# Cyclone_Keychain_SSOP28.net
KiCad netlist of a schematic drawn in EAGLE
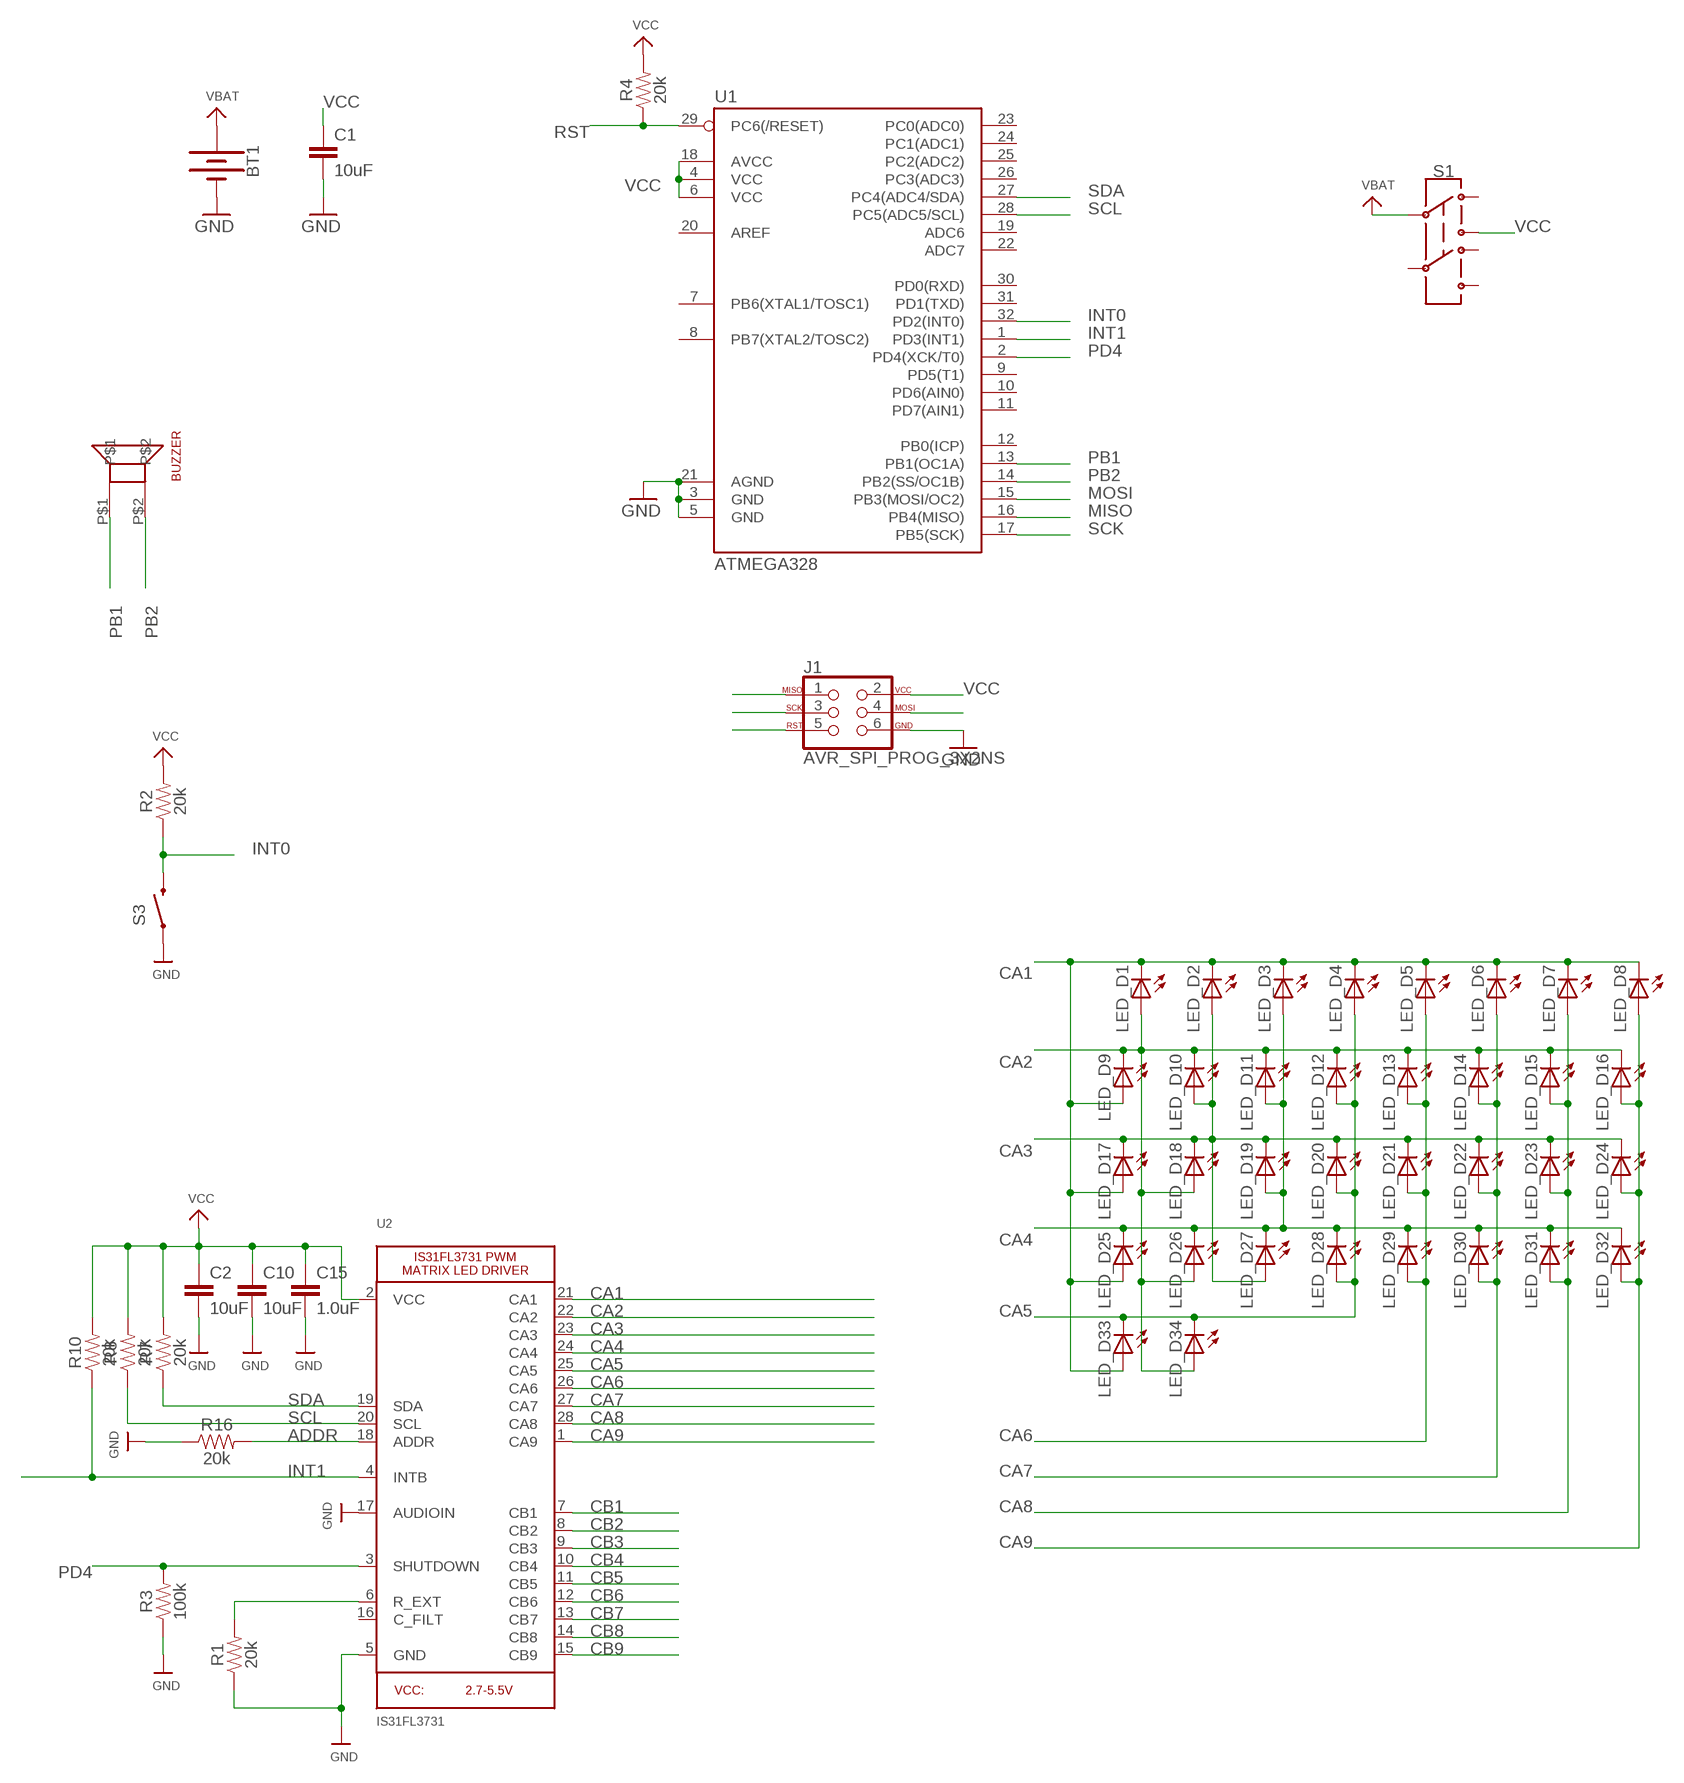
[diagram p0: schematic, sheet 1]

(export (version "E")
  (design (tool "Eeschema 10.0.6"))
  (components
    (comp (ref "BT1")
      (value "BATTERY-20MM_PTH_WIDEPOS")
      (footprint "eagle-import:BATTCOM_20MM_PTH_WIDEPOS")
      (libsource (lib "eagle-import") (part "BATTERY-20MM_PTH_WIDEPOS"))
    )
    (comp (ref "C1")
      (value "10uF")
      (footprint "eagle-import:0805")
      (libsource (lib "eagle-import") (part "10UF-0805-10V-10%"))
    )
    (comp (ref "C2")
      (value "10uF")
      (footprint "eagle-import:0805")
      (libsource (lib "eagle-import") (part "10UF-0805-10V-10%"))
    )
    (comp (ref "C10")
      (value "10uF")
      (footprint "eagle-import:0805")
      (libsource (lib "eagle-import") (part "10UF-0805-10V-10%"))
    )
    (comp (ref "C15")
      (value "1.0uF")
      (footprint "eagle-import:0805")
      (libsource (lib "eagle-import") (part "1.0UF-0805-25V-10%"))
    )
    (comp (ref "J1")
      (value "AVR_SPI_PROG_3X2NS")
      (footprint "eagle-import:2X3-NS")
      (libsource (lib "eagle-import") (part "AVR_SPI_PROG_3X2NS"))
    )
    (comp (ref "LED_D1")
      (value "LEDCHIP-LED0805")
      (footprint "eagle-import:CHIP-LED0805")
      (libsource (lib "eagle-import") (part "LEDCHIP-LED0805"))
    )
    (comp (ref "LED_D2")
      (value "LEDCHIP-LED0805")
      (footprint "eagle-import:CHIP-LED0805")
      (libsource (lib "eagle-import") (part "LEDCHIP-LED0805"))
    )
    (comp (ref "LED_D3")
      (value "LEDCHIP-LED0805")
      (footprint "eagle-import:CHIP-LED0805")
      (libsource (lib "eagle-import") (part "LEDCHIP-LED0805"))
    )
    (comp (ref "LED_D4")
      (value "LEDCHIP-LED0805")
      (footprint "eagle-import:CHIP-LED0805")
      (libsource (lib "eagle-import") (part "LEDCHIP-LED0805"))
    )
    (comp (ref "LED_D5")
      (value "LEDCHIP-LED0805")
      (footprint "eagle-import:CHIP-LED0805")
      (libsource (lib "eagle-import") (part "LEDCHIP-LED0805"))
    )
    (comp (ref "LED_D6")
      (value "LEDCHIP-LED0805")
      (footprint "eagle-import:CHIP-LED0805")
      (libsource (lib "eagle-import") (part "LEDCHIP-LED0805"))
    )
    (comp (ref "LED_D7")
      (value "LEDCHIP-LED0805")
      (footprint "eagle-import:CHIP-LED0805")
      (libsource (lib "eagle-import") (part "LEDCHIP-LED0805"))
    )
    (comp (ref "LED_D8")
      (value "LEDCHIP-LED0805")
      (footprint "eagle-import:CHIP-LED0805")
      (libsource (lib "eagle-import") (part "LEDCHIP-LED0805"))
    )
    (comp (ref "LED_D9")
      (value "LEDCHIP-LED0805")
      (footprint "eagle-import:CHIP-LED0805")
      (libsource (lib "eagle-import") (part "LEDCHIP-LED0805"))
    )
    (comp (ref "LED_D10")
      (value "LEDCHIP-LED0805")
      (footprint "eagle-import:CHIP-LED0805")
      (libsource (lib "eagle-import") (part "LEDCHIP-LED0805"))
    )
    (comp (ref "LED_D11")
      (value "LEDCHIP-LED0805")
      (footprint "eagle-import:CHIP-LED0805")
      (libsource (lib "eagle-import") (part "LEDCHIP-LED0805"))
    )
    (comp (ref "LED_D12")
      (value "LEDCHIP-LED0805")
      (footprint "eagle-import:CHIP-LED0805")
      (libsource (lib "eagle-import") (part "LEDCHIP-LED0805"))
    )
    (comp (ref "LED_D13")
      (value "LEDCHIP-LED0805")
      (footprint "eagle-import:CHIP-LED0805")
      (libsource (lib "eagle-import") (part "LEDCHIP-LED0805"))
    )
    (comp (ref "LED_D14")
      (value "LEDCHIP-LED0805")
      (footprint "eagle-import:CHIP-LED0805")
      (libsource (lib "eagle-import") (part "LEDCHIP-LED0805"))
    )
    (comp (ref "LED_D15")
      (value "LEDCHIP-LED0805")
      (footprint "eagle-import:CHIP-LED0805")
      (libsource (lib "eagle-import") (part "LEDCHIP-LED0805"))
    )
    (comp (ref "LED_D16")
      (value "LEDCHIP-LED0805")
      (footprint "eagle-import:CHIP-LED0805")
      (libsource (lib "eagle-import") (part "LEDCHIP-LED0805"))
    )
    (comp (ref "LED_D17")
      (value "LEDCHIP-LED0805")
      (footprint "eagle-import:CHIP-LED0805")
      (libsource (lib "eagle-import") (part "LEDCHIP-LED0805"))
    )
    (comp (ref "LED_D18")
      (value "LEDCHIP-LED0805")
      (footprint "eagle-import:CHIP-LED0805")
      (libsource (lib "eagle-import") (part "LEDCHIP-LED0805"))
    )
    (comp (ref "LED_D19")
      (value "LEDCHIP-LED0805")
      (footprint "eagle-import:CHIP-LED0805")
      (libsource (lib "eagle-import") (part "LEDCHIP-LED0805"))
    )
    (comp (ref "LED_D20")
      (value "LEDCHIP-LED0805")
      (footprint "eagle-import:CHIP-LED0805")
      (libsource (lib "eagle-import") (part "LEDCHIP-LED0805"))
    )
    (comp (ref "LED_D21")
      (value "LEDCHIP-LED0805")
      (footprint "eagle-import:CHIP-LED0805")
      (libsource (lib "eagle-import") (part "LEDCHIP-LED0805"))
    )
    (comp (ref "LED_D22")
      (value "LEDCHIP-LED0805")
      (footprint "eagle-import:CHIP-LED0805")
      (libsource (lib "eagle-import") (part "LEDCHIP-LED0805"))
    )
    (comp (ref "LED_D23")
      (value "LEDCHIP-LED0805")
      (footprint "eagle-import:CHIP-LED0805")
      (libsource (lib "eagle-import") (part "LEDCHIP-LED0805"))
    )
    (comp (ref "LED_D24")
      (value "LEDCHIP-LED0805")
      (footprint "eagle-import:CHIP-LED0805")
      (libsource (lib "eagle-import") (part "LEDCHIP-LED0805"))
    )
    (comp (ref "LED_D25")
      (value "LEDCHIP-LED0805")
      (footprint "eagle-import:CHIP-LED0805")
      (libsource (lib "eagle-import") (part "LEDCHIP-LED0805"))
    )
    (comp (ref "LED_D26")
      (value "LEDCHIP-LED0805")
      (footprint "eagle-import:CHIP-LED0805")
      (libsource (lib "eagle-import") (part "LEDCHIP-LED0805"))
    )
    (comp (ref "LED_D27")
      (value "LEDCHIP-LED0805")
      (footprint "eagle-import:CHIP-LED0805")
      (libsource (lib "eagle-import") (part "LEDCHIP-LED0805"))
    )
    (comp (ref "LED_D28")
      (value "LEDCHIP-LED0805")
      (footprint "eagle-import:CHIP-LED0805")
      (libsource (lib "eagle-import") (part "LEDCHIP-LED0805"))
    )
    (comp (ref "LED_D29")
      (value "LEDCHIP-LED0805")
      (footprint "eagle-import:CHIP-LED0805")
      (libsource (lib "eagle-import") (part "LEDCHIP-LED0805"))
    )
    (comp (ref "LED_D30")
      (value "LEDCHIP-LED0805")
      (footprint "eagle-import:CHIP-LED0805")
      (libsource (lib "eagle-import") (part "LEDCHIP-LED0805"))
    )
    (comp (ref "LED_D31")
      (value "LEDCHIP-LED0805")
      (footprint "eagle-import:CHIP-LED0805")
      (libsource (lib "eagle-import") (part "LEDCHIP-LED0805"))
    )
    (comp (ref "LED_D32")
      (value "LEDCHIP-LED0805")
      (footprint "eagle-import:CHIP-LED0805")
      (libsource (lib "eagle-import") (part "LEDCHIP-LED0805"))
    )
    (comp (ref "LED_D33")
      (value "LEDCHIP-LED0805")
      (footprint "eagle-import:CHIP-LED0805")
      (libsource (lib "eagle-import") (part "LEDCHIP-LED0805"))
    )
    (comp (ref "LED_D34")
      (value "LEDCHIP-LED0805")
      (footprint "eagle-import:CHIP-LED0805")
      (libsource (lib "eagle-import") (part "LEDCHIP-LED0805"))
    )
    (comp (ref "R1")
      (value "20k")
      (footprint "eagle-import:0805")
      (libsource (lib "eagle-import") (part "20KOHM-0805-1/8W-5%"))
    )
    (comp (ref "R2")
      (value "20k")
      (footprint "eagle-import:0805")
      (libsource (lib "eagle-import") (part "20KOHM-0805-1/8W-5%"))
    )
    (comp (ref "R3")
      (value "100k")
      (footprint "eagle-import:0805")
      (libsource (lib "eagle-import") (part "20KOHM-0805-1/8W-5%"))
    )
    (comp (ref "R4")
      (value "20k")
      (footprint "eagle-import:0805")
      (libsource (lib "eagle-import") (part "20KOHM-0805-1/8W-5%"))
    )
    (comp (ref "R7")
      (value "20k")
      (footprint "eagle-import:0805")
      (libsource (lib "eagle-import") (part "20KOHM-0805-1/8W-5%"))
    )
    (comp (ref "R8")
      (value "20k")
      (footprint "eagle-import:0805")
      (libsource (lib "eagle-import") (part "20KOHM-0805-1/8W-5%"))
    )
    (comp (ref "R10")
      (value "20k")
      (footprint "eagle-import:0805")
      (libsource (lib "eagle-import") (part "20KOHM-0805-1/8W-5%"))
    )
    (comp (ref "R16")
      (value "20k")
      (footprint "eagle-import:0805")
      (libsource (lib "eagle-import") (part "20KOHM-0805-1/8W-5%"))
    )
    (comp (ref "S1")
      (value "SWITCH-DPDT-SMD-AYZ0202")
      (footprint "eagle-import:SWITCH_DPDT_SMD_AYZ0202")
      (libsource (lib "eagle-import") (part "SWITCH-DPDT-SMD-AYZ0202"))
    )
    (comp (ref "S3")
      (value "SWITCH-MOMENTARY-2SMD")
      (footprint "eagle-import:TACTILE_SWITCH_SMD")
      (libsource (lib "eagle-import") (part "SWITCH-MOMENTARY-2SMD"))
    )
    (comp (ref "U$11")
      (value "PIEZO_BUZZER_SMT")
      (footprint "eagle-import:PIEZO_BUZZER_SMT")
      (libsource (lib "eagle-import") (part "PIEZO_BUZZER_SMT"))
    )
    (comp (ref "U1")
      (value "ATMEGA328")
      (footprint "eagle-import:TQFP32-08")
      (libsource (lib "eagle-import") (part "ATMEGA328P_TQFP"))
    )
    (comp (ref "U2")
      (value "IS31FL3731")
      (footprint "eagle-import:SSOP28DB")
      (libsource (lib "eagle-import") (part "IS31FL3731SSOP"))
    )
  )
  (nets
    (net (code "1") (name "/ADDR") (class "Default")
      (node (ref "R16") (pin "2") (pinfunction "2_2") (pintype "passive"))
      (node (ref "U2") (pin "18") (pinfunction "ADDR_18") (pintype "bidirectional"))
    )
    (net (code "2") (name "/CA1") (class "Default")
      (node (ref "LED_D1") (pin "C") (pinfunction "C_C") (pintype "passive"))
      (node (ref "LED_D17") (pin "A") (pinfunction "A_A") (pintype "passive"))
      (node (ref "LED_D2") (pin "C") (pinfunction "C_C") (pintype "passive"))
      (node (ref "LED_D25") (pin "A") (pinfunction "A_A") (pintype "passive"))
      (node (ref "LED_D3") (pin "C") (pinfunction "C_C") (pintype "passive"))
      (node (ref "LED_D33") (pin "A") (pinfunction "A_A") (pintype "passive"))
      (node (ref "LED_D4") (pin "C") (pinfunction "C_C") (pintype "passive"))
      (node (ref "LED_D5") (pin "C") (pinfunction "C_C") (pintype "passive"))
      (node (ref "LED_D6") (pin "C") (pinfunction "C_C") (pintype "passive"))
      (node (ref "LED_D7") (pin "C") (pinfunction "C_C") (pintype "passive"))
      (node (ref "LED_D8") (pin "C") (pinfunction "C_C") (pintype "passive"))
      (node (ref "LED_D9") (pin "A") (pinfunction "A_A") (pintype "passive"))
      (node (ref "U2") (pin "21") (pinfunction "CA1_21") (pintype "bidirectional"))
    )
    (net (code "3") (name "/CA2") (class "Default")
      (node (ref "LED_D1") (pin "A") (pinfunction "A_A") (pintype "passive"))
      (node (ref "LED_D10") (pin "C") (pinfunction "C_C") (pintype "passive"))
      (node (ref "LED_D11") (pin "C") (pinfunction "C_C") (pintype "passive"))
      (node (ref "LED_D12") (pin "C") (pinfunction "C_C") (pintype "passive"))
      (node (ref "LED_D13") (pin "C") (pinfunction "C_C") (pintype "passive"))
      (node (ref "LED_D14") (pin "C") (pinfunction "C_C") (pintype "passive"))
      (node (ref "LED_D15") (pin "C") (pinfunction "C_C") (pintype "passive"))
      (node (ref "LED_D16") (pin "C") (pinfunction "C_C") (pintype "passive"))
      (node (ref "LED_D18") (pin "A") (pinfunction "A_A") (pintype "passive"))
      (node (ref "LED_D26") (pin "A") (pinfunction "A_A") (pintype "passive"))
      (node (ref "LED_D34") (pin "A") (pinfunction "A_A") (pintype "passive"))
      (node (ref "LED_D9") (pin "C") (pinfunction "C_C") (pintype "passive"))
      (node (ref "U2") (pin "22") (pinfunction "CA2_22") (pintype "bidirectional"))
    )
    (net (code "4") (name "/CA3") (class "Default")
      (node (ref "LED_D10") (pin "A") (pinfunction "A_A") (pintype "passive"))
      (node (ref "LED_D17") (pin "C") (pinfunction "C_C") (pintype "passive"))
      (node (ref "LED_D18") (pin "C") (pinfunction "C_C") (pintype "passive"))
      (node (ref "LED_D19") (pin "C") (pinfunction "C_C") (pintype "passive"))
      (node (ref "LED_D2") (pin "A") (pinfunction "A_A") (pintype "passive"))
      (node (ref "LED_D20") (pin "C") (pinfunction "C_C") (pintype "passive"))
      (node (ref "LED_D21") (pin "C") (pinfunction "C_C") (pintype "passive"))
      (node (ref "LED_D22") (pin "C") (pinfunction "C_C") (pintype "passive"))
      (node (ref "LED_D23") (pin "C") (pinfunction "C_C") (pintype "passive"))
      (node (ref "LED_D24") (pin "C") (pinfunction "C_C") (pintype "passive"))
      (node (ref "LED_D27") (pin "A") (pinfunction "A_A") (pintype "passive"))
      (node (ref "U2") (pin "23") (pinfunction "CA3_23") (pintype "bidirectional"))
    )
    (net (code "5") (name "/CA4") (class "Default")
      (node (ref "LED_D11") (pin "A") (pinfunction "A_A") (pintype "passive"))
      (node (ref "LED_D19") (pin "A") (pinfunction "A_A") (pintype "passive"))
      (node (ref "LED_D25") (pin "C") (pinfunction "C_C") (pintype "passive"))
      (node (ref "LED_D26") (pin "C") (pinfunction "C_C") (pintype "passive"))
      (node (ref "LED_D27") (pin "C") (pinfunction "C_C") (pintype "passive"))
      (node (ref "LED_D28") (pin "C") (pinfunction "C_C") (pintype "passive"))
      (node (ref "LED_D29") (pin "C") (pinfunction "C_C") (pintype "passive"))
      (node (ref "LED_D3") (pin "A") (pinfunction "A_A") (pintype "passive"))
      (node (ref "LED_D30") (pin "C") (pinfunction "C_C") (pintype "passive"))
      (node (ref "LED_D31") (pin "C") (pinfunction "C_C") (pintype "passive"))
      (node (ref "LED_D32") (pin "C") (pinfunction "C_C") (pintype "passive"))
      (node (ref "U2") (pin "24") (pinfunction "CA4_24") (pintype "bidirectional"))
    )
    (net (code "6") (name "/CA5") (class "Default")
      (node (ref "LED_D12") (pin "A") (pinfunction "A_A") (pintype "passive"))
      (node (ref "LED_D20") (pin "A") (pinfunction "A_A") (pintype "passive"))
      (node (ref "LED_D28") (pin "A") (pinfunction "A_A") (pintype "passive"))
      (node (ref "LED_D33") (pin "C") (pinfunction "C_C") (pintype "passive"))
      (node (ref "LED_D34") (pin "C") (pinfunction "C_C") (pintype "passive"))
      (node (ref "LED_D4") (pin "A") (pinfunction "A_A") (pintype "passive"))
      (node (ref "U2") (pin "25") (pinfunction "CA5_25") (pintype "bidirectional"))
    )
    (net (code "7") (name "/CA6") (class "Default")
      (node (ref "LED_D13") (pin "A") (pinfunction "A_A") (pintype "passive"))
      (node (ref "LED_D21") (pin "A") (pinfunction "A_A") (pintype "passive"))
      (node (ref "LED_D29") (pin "A") (pinfunction "A_A") (pintype "passive"))
      (node (ref "LED_D5") (pin "A") (pinfunction "A_A") (pintype "passive"))
      (node (ref "U2") (pin "26") (pinfunction "CA6_26") (pintype "bidirectional"))
    )
    (net (code "8") (name "/CA7") (class "Default")
      (node (ref "LED_D14") (pin "A") (pinfunction "A_A") (pintype "passive"))
      (node (ref "LED_D22") (pin "A") (pinfunction "A_A") (pintype "passive"))
      (node (ref "LED_D30") (pin "A") (pinfunction "A_A") (pintype "passive"))
      (node (ref "LED_D6") (pin "A") (pinfunction "A_A") (pintype "passive"))
      (node (ref "U2") (pin "27") (pinfunction "CA7_27") (pintype "bidirectional"))
    )
    (net (code "9") (name "/CA8") (class "Default")
      (node (ref "LED_D15") (pin "A") (pinfunction "A_A") (pintype "passive"))
      (node (ref "LED_D23") (pin "A") (pinfunction "A_A") (pintype "passive"))
      (node (ref "LED_D31") (pin "A") (pinfunction "A_A") (pintype "passive"))
      (node (ref "LED_D7") (pin "A") (pinfunction "A_A") (pintype "passive"))
      (node (ref "U2") (pin "28") (pinfunction "CA8_28") (pintype "bidirectional"))
    )
    (net (code "10") (name "/CA9") (class "Default")
      (node (ref "LED_D16") (pin "A") (pinfunction "A_A") (pintype "passive"))
      (node (ref "LED_D24") (pin "A") (pinfunction "A_A") (pintype "passive"))
      (node (ref "LED_D32") (pin "A") (pinfunction "A_A") (pintype "passive"))
      (node (ref "LED_D8") (pin "A") (pinfunction "A_A") (pintype "passive"))
      (node (ref "U2") (pin "1") (pinfunction "CA9_1") (pintype "bidirectional"))
    )
    (net (code "11") (name "/CB1") (class "Default")
      (node (ref "U2") (pin "7") (pinfunction "CB1_7") (pintype "bidirectional"))
    )
    (net (code "12") (name "/CB2") (class "Default")
      (node (ref "U2") (pin "8") (pinfunction "CB2_8") (pintype "bidirectional"))
    )
    (net (code "13") (name "/CB3") (class "Default")
      (node (ref "U2") (pin "9") (pinfunction "CB3_9") (pintype "bidirectional"))
    )
    (net (code "14") (name "/CB4") (class "Default")
      (node (ref "U2") (pin "10") (pinfunction "CB4_10") (pintype "bidirectional"))
    )
    (net (code "15") (name "/CB5") (class "Default")
      (node (ref "U2") (pin "11") (pinfunction "CB5_11") (pintype "bidirectional"))
    )
    (net (code "16") (name "/CB6") (class "Default")
      (node (ref "U2") (pin "12") (pinfunction "CB6_12") (pintype "bidirectional"))
    )
    (net (code "17") (name "/CB7") (class "Default")
      (node (ref "U2") (pin "13") (pinfunction "CB7_13") (pintype "bidirectional"))
    )
    (net (code "18") (name "/CB8") (class "Default")
      (node (ref "U2") (pin "14") (pinfunction "CB8_14") (pintype "bidirectional"))
    )
    (net (code "19") (name "/CB9") (class "Default")
      (node (ref "U2") (pin "15") (pinfunction "CB9_15") (pintype "bidirectional"))
    )
    (net (code "20") (name "/INT0") (class "Default")
      (node (ref "R2") (pin "1") (pinfunction "1_1") (pintype "passive"))
      (node (ref "S3") (pin "3") (pinfunction "2_3") (pintype "passive"))
      (node (ref "U1") (pin "32") (pinfunction "PD2(INT0)_32") (pintype "bidirectional"))
    )
    (net (code "21") (name "/INT1") (class "Default")
      (node (ref "R10") (pin "1") (pinfunction "1_1") (pintype "passive"))
      (node (ref "U1") (pin "1") (pinfunction "PD3(INT1)_1") (pintype "bidirectional"))
      (node (ref "U2") (pin "4") (pinfunction "INTB_4") (pintype "output"))
    )
    (net (code "22") (name "/MISO") (class "Default")
      (node (ref "J1") (pin "1") (pinfunction "1_1") (pintype "passive"))
      (node (ref "U1") (pin "16") (pinfunction "PB4(MISO)_16") (pintype "bidirectional"))
    )
    (net (code "23") (name "/MOSI") (class "Default")
      (node (ref "J1") (pin "4") (pinfunction "4_4") (pintype "passive"))
      (node (ref "U1") (pin "15") (pinfunction "PB3(MOSI/OC2)_15") (pintype "bidirectional"))
    )
    (net (code "24") (name "/PB1") (class "Default")
      (node (ref "U$11") (pin "P$1") (pinfunction "P$1_P$1") (pintype "bidirectional"))
      (node (ref "U1") (pin "13") (pinfunction "PB1(OC1A)_13") (pintype "bidirectional"))
    )
    (net (code "25") (name "/PB2") (class "Default")
      (node (ref "U$11") (pin "P$2") (pinfunction "P$2_P$2") (pintype "bidirectional"))
      (node (ref "U1") (pin "14") (pinfunction "PB2(SS/OC1B)_14") (pintype "bidirectional"))
    )
    (net (code "26") (name "/PD4") (class "Default")
      (node (ref "R3") (pin "2") (pinfunction "2_2") (pintype "passive"))
      (node (ref "U1") (pin "2") (pinfunction "PD4(XCK/T0)_2") (pintype "bidirectional"))
      (node (ref "U2") (pin "3") (pinfunction "SHUTDOWN_3") (pintype "input"))
    )
    (net (code "27") (name "/RST") (class "Default")
      (node (ref "J1") (pin "5") (pinfunction "5_5") (pintype "passive"))
      (node (ref "R4") (pin "1") (pinfunction "1_1") (pintype "passive"))
      (node (ref "U1") (pin "29") (pinfunction "PC6(/RESET)_29") (pintype "bidirectional"))
    )
    (net (code "28") (name "/SCK") (class "Default")
      (node (ref "J1") (pin "3") (pinfunction "3_3") (pintype "passive"))
      (node (ref "U1") (pin "17") (pinfunction "PB5(SCK)_17") (pintype "bidirectional"))
    )
    (net (code "29") (name "/SCL") (class "Default")
      (node (ref "R8") (pin "1") (pinfunction "1_1") (pintype "passive"))
      (node (ref "U1") (pin "28") (pinfunction "PC5(ADC5/SCL)_28") (pintype "bidirectional"))
      (node (ref "U2") (pin "20") (pinfunction "SCL_20") (pintype "bidirectional"))
    )
    (net (code "30") (name "/SDA") (class "Default")
      (node (ref "R7") (pin "1") (pinfunction "1_1") (pintype "passive"))
      (node (ref "U1") (pin "27") (pinfunction "PC4(ADC4/SDA)_27") (pintype "bidirectional"))
      (node (ref "U2") (pin "19") (pinfunction "SDA_19") (pintype "bidirectional"))
    )
    (net (code "31") (name "GND") (class "Default")
      (node (ref "BT1") (pin "2") (pinfunction "-_2") (pintype "power_in"))
      (node (ref "C1") (pin "2") (pinfunction "2_2") (pintype "passive"))
      (node (ref "C10") (pin "2") (pinfunction "2_2") (pintype "passive"))
      (node (ref "C15") (pin "2") (pinfunction "2_2") (pintype "passive"))
      (node (ref "C2") (pin "2") (pinfunction "2_2") (pintype "passive"))
      (node (ref "J1") (pin "6") (pinfunction "6_6") (pintype "passive"))
      (node (ref "R1") (pin "1") (pinfunction "1_1") (pintype "passive"))
      (node (ref "R16") (pin "1") (pinfunction "1_1") (pintype "passive"))
      (node (ref "R3") (pin "1") (pinfunction "1_1") (pintype "passive"))
      (node (ref "S3") (pin "1") (pinfunction "1_1") (pintype "passive"))
      (node (ref "U1") (pin "21") (pinfunction "AGND_21") (pintype "bidirectional"))
      (node (ref "U1") (pin "3") (pinfunction "GND_3") (pintype "bidirectional"))
      (node (ref "U1") (pin "5") (pinfunction "GND_5") (pintype "bidirectional"))
      (node (ref "U2") (pin "17") (pinfunction "AUDIOIN_17") (pintype "input"))
      (node (ref "U2") (pin "5") (pinfunction "GND_5") (pintype "power_in"))
    )
    (net (code "32") (name "Net-(U2-R_EXT)") (class "Default")
      (node (ref "R1") (pin "2") (pinfunction "2_2") (pintype "passive"))
      (node (ref "U2") (pin "6") (pinfunction "R_EXT_6") (pintype "bidirectional"))
    )
    (net (code "33") (name "VBAT") (class "Default")
      (node (ref "BT1") (pin "1") (pinfunction "+_1") (pintype "power_in"))
      (node (ref "S1") (pin "2") (pinfunction "2_2") (pintype "bidirectional"))
    )
    (net (code "34") (name "VCC") (class "Default")
      (node (ref "C1") (pin "1") (pinfunction "1_1") (pintype "passive"))
      (node (ref "C10") (pin "1") (pinfunction "1_1") (pintype "passive"))
      (node (ref "C15") (pin "1") (pinfunction "1_1") (pintype "passive"))
      (node (ref "C2") (pin "1") (pinfunction "1_1") (pintype "passive"))
      (node (ref "J1") (pin "2") (pinfunction "2_2") (pintype "passive"))
      (node (ref "R10") (pin "2") (pinfunction "2_2") (pintype "passive"))
      (node (ref "R2") (pin "2") (pinfunction "2_2") (pintype "passive"))
      (node (ref "R4") (pin "2") (pinfunction "2_2") (pintype "passive"))
      (node (ref "R7") (pin "2") (pinfunction "2_2") (pintype "passive"))
      (node (ref "R8") (pin "2") (pinfunction "2_2") (pintype "passive"))
      (node (ref "S1") (pin "3") (pinfunction "3_3") (pintype "bidirectional"))
      (node (ref "U1") (pin "18") (pinfunction "AVCC_18") (pintype "bidirectional"))
      (node (ref "U1") (pin "4") (pinfunction "VCC_4") (pintype "bidirectional"))
      (node (ref "U1") (pin "6") (pinfunction "VCC_6") (pintype "bidirectional"))
      (node (ref "U2") (pin "2") (pinfunction "VCC_2") (pintype "power_in"))
    )
    (net (code "35") (name "unconnected-(S1-Pad1)") (class "Default")
      (node (ref "S1") (pin "1") (pinfunction "1_1") (pintype "bidirectional"))
    )
    (net (code "36") (name "unconnected-(S1-Pad4)") (class "Default")
      (node (ref "S1") (pin "4") (pinfunction "4_4") (pintype "bidirectional"))
    )
    (net (code "37") (name "unconnected-(S1-Pad5)") (class "Default")
      (node (ref "S1") (pin "5") (pinfunction "5_5") (pintype "bidirectional"))
    )
    (net (code "38") (name "unconnected-(S1-Pad6)") (class "Default")
      (node (ref "S1") (pin "6") (pinfunction "6_6") (pintype "bidirectional"))
    )
    (net (code "39") (name "unconnected-(U1-ADC6-Pad19)") (class "Default")
      (node (ref "U1") (pin "19") (pinfunction "ADC6_19") (pintype "bidirectional"))
    )
    (net (code "40") (name "unconnected-(U1-ADC7-Pad22)") (class "Default")
      (node (ref "U1") (pin "22") (pinfunction "ADC7_22") (pintype "bidirectional"))
    )
    (net (code "41") (name "unconnected-(U1-AREF-Pad20)") (class "Default")
      (node (ref "U1") (pin "20") (pinfunction "AREF_20") (pintype "bidirectional"))
    )
    (net (code "42") (name "unconnected-(U1-PB0(ICP)-Pad12)") (class "Default")
      (node (ref "U1") (pin "12") (pinfunction "PB0(ICP)_12") (pintype "bidirectional"))
    )
    (net (code "43") (name "unconnected-(U1-PB6(XTAL1{slash}TOSC1)-Pad7)") (class "Default")
      (node (ref "U1") (pin "7") (pinfunction "PB6(XTAL1/TOSC1)_7") (pintype "bidirectional"))
    )
    (net (code "44") (name "unconnected-(U1-PB7(XTAL2{slash}TOSC2)-Pad8)") (class "Default")
      (node (ref "U1") (pin "8") (pinfunction "PB7(XTAL2/TOSC2)_8") (pintype "bidirectional"))
    )
    (net (code "45") (name "unconnected-(U1-PC0(ADC0)-Pad23)") (class "Default")
      (node (ref "U1") (pin "23") (pinfunction "PC0(ADC0)_23") (pintype "bidirectional"))
    )
    (net (code "46") (name "unconnected-(U1-PC1(ADC1)-Pad24)") (class "Default")
      (node (ref "U1") (pin "24") (pinfunction "PC1(ADC1)_24") (pintype "bidirectional"))
    )
    (net (code "47") (name "unconnected-(U1-PC2(ADC2)-Pad25)") (class "Default")
      (node (ref "U1") (pin "25") (pinfunction "PC2(ADC2)_25") (pintype "bidirectional"))
    )
    (net (code "48") (name "unconnected-(U1-PC3(ADC3)-Pad26)") (class "Default")
      (node (ref "U1") (pin "26") (pinfunction "PC3(ADC3)_26") (pintype "bidirectional"))
    )
    (net (code "49") (name "unconnected-(U1-PD0(RXD)-Pad30)") (class "Default")
      (node (ref "U1") (pin "30") (pinfunction "PD0(RXD)_30") (pintype "bidirectional"))
    )
    (net (code "50") (name "unconnected-(U1-PD1(TXD)-Pad31)") (class "Default")
      (node (ref "U1") (pin "31") (pinfunction "PD1(TXD)_31") (pintype "bidirectional"))
    )
    (net (code "51") (name "unconnected-(U1-PD5(T1)-Pad9)") (class "Default")
      (node (ref "U1") (pin "9") (pinfunction "PD5(T1)_9") (pintype "bidirectional"))
    )
    (net (code "52") (name "unconnected-(U1-PD6(AIN0)-Pad10)") (class "Default")
      (node (ref "U1") (pin "10") (pinfunction "PD6(AIN0)_10") (pintype "bidirectional"))
    )
    (net (code "53") (name "unconnected-(U1-PD7(AIN1)-Pad11)") (class "Default")
      (node (ref "U1") (pin "11") (pinfunction "PD7(AIN1)_11") (pintype "bidirectional"))
    )
    (net (code "54") (name "unconnected-(U2-C_FILT-Pad16)") (class "Default")
      (node (ref "U2") (pin "16") (pinfunction "C_FILT_16") (pintype "bidirectional"))
    )
  )
)
